# ps2.net
KiCad netlist of a schematic drawn in EAGLE
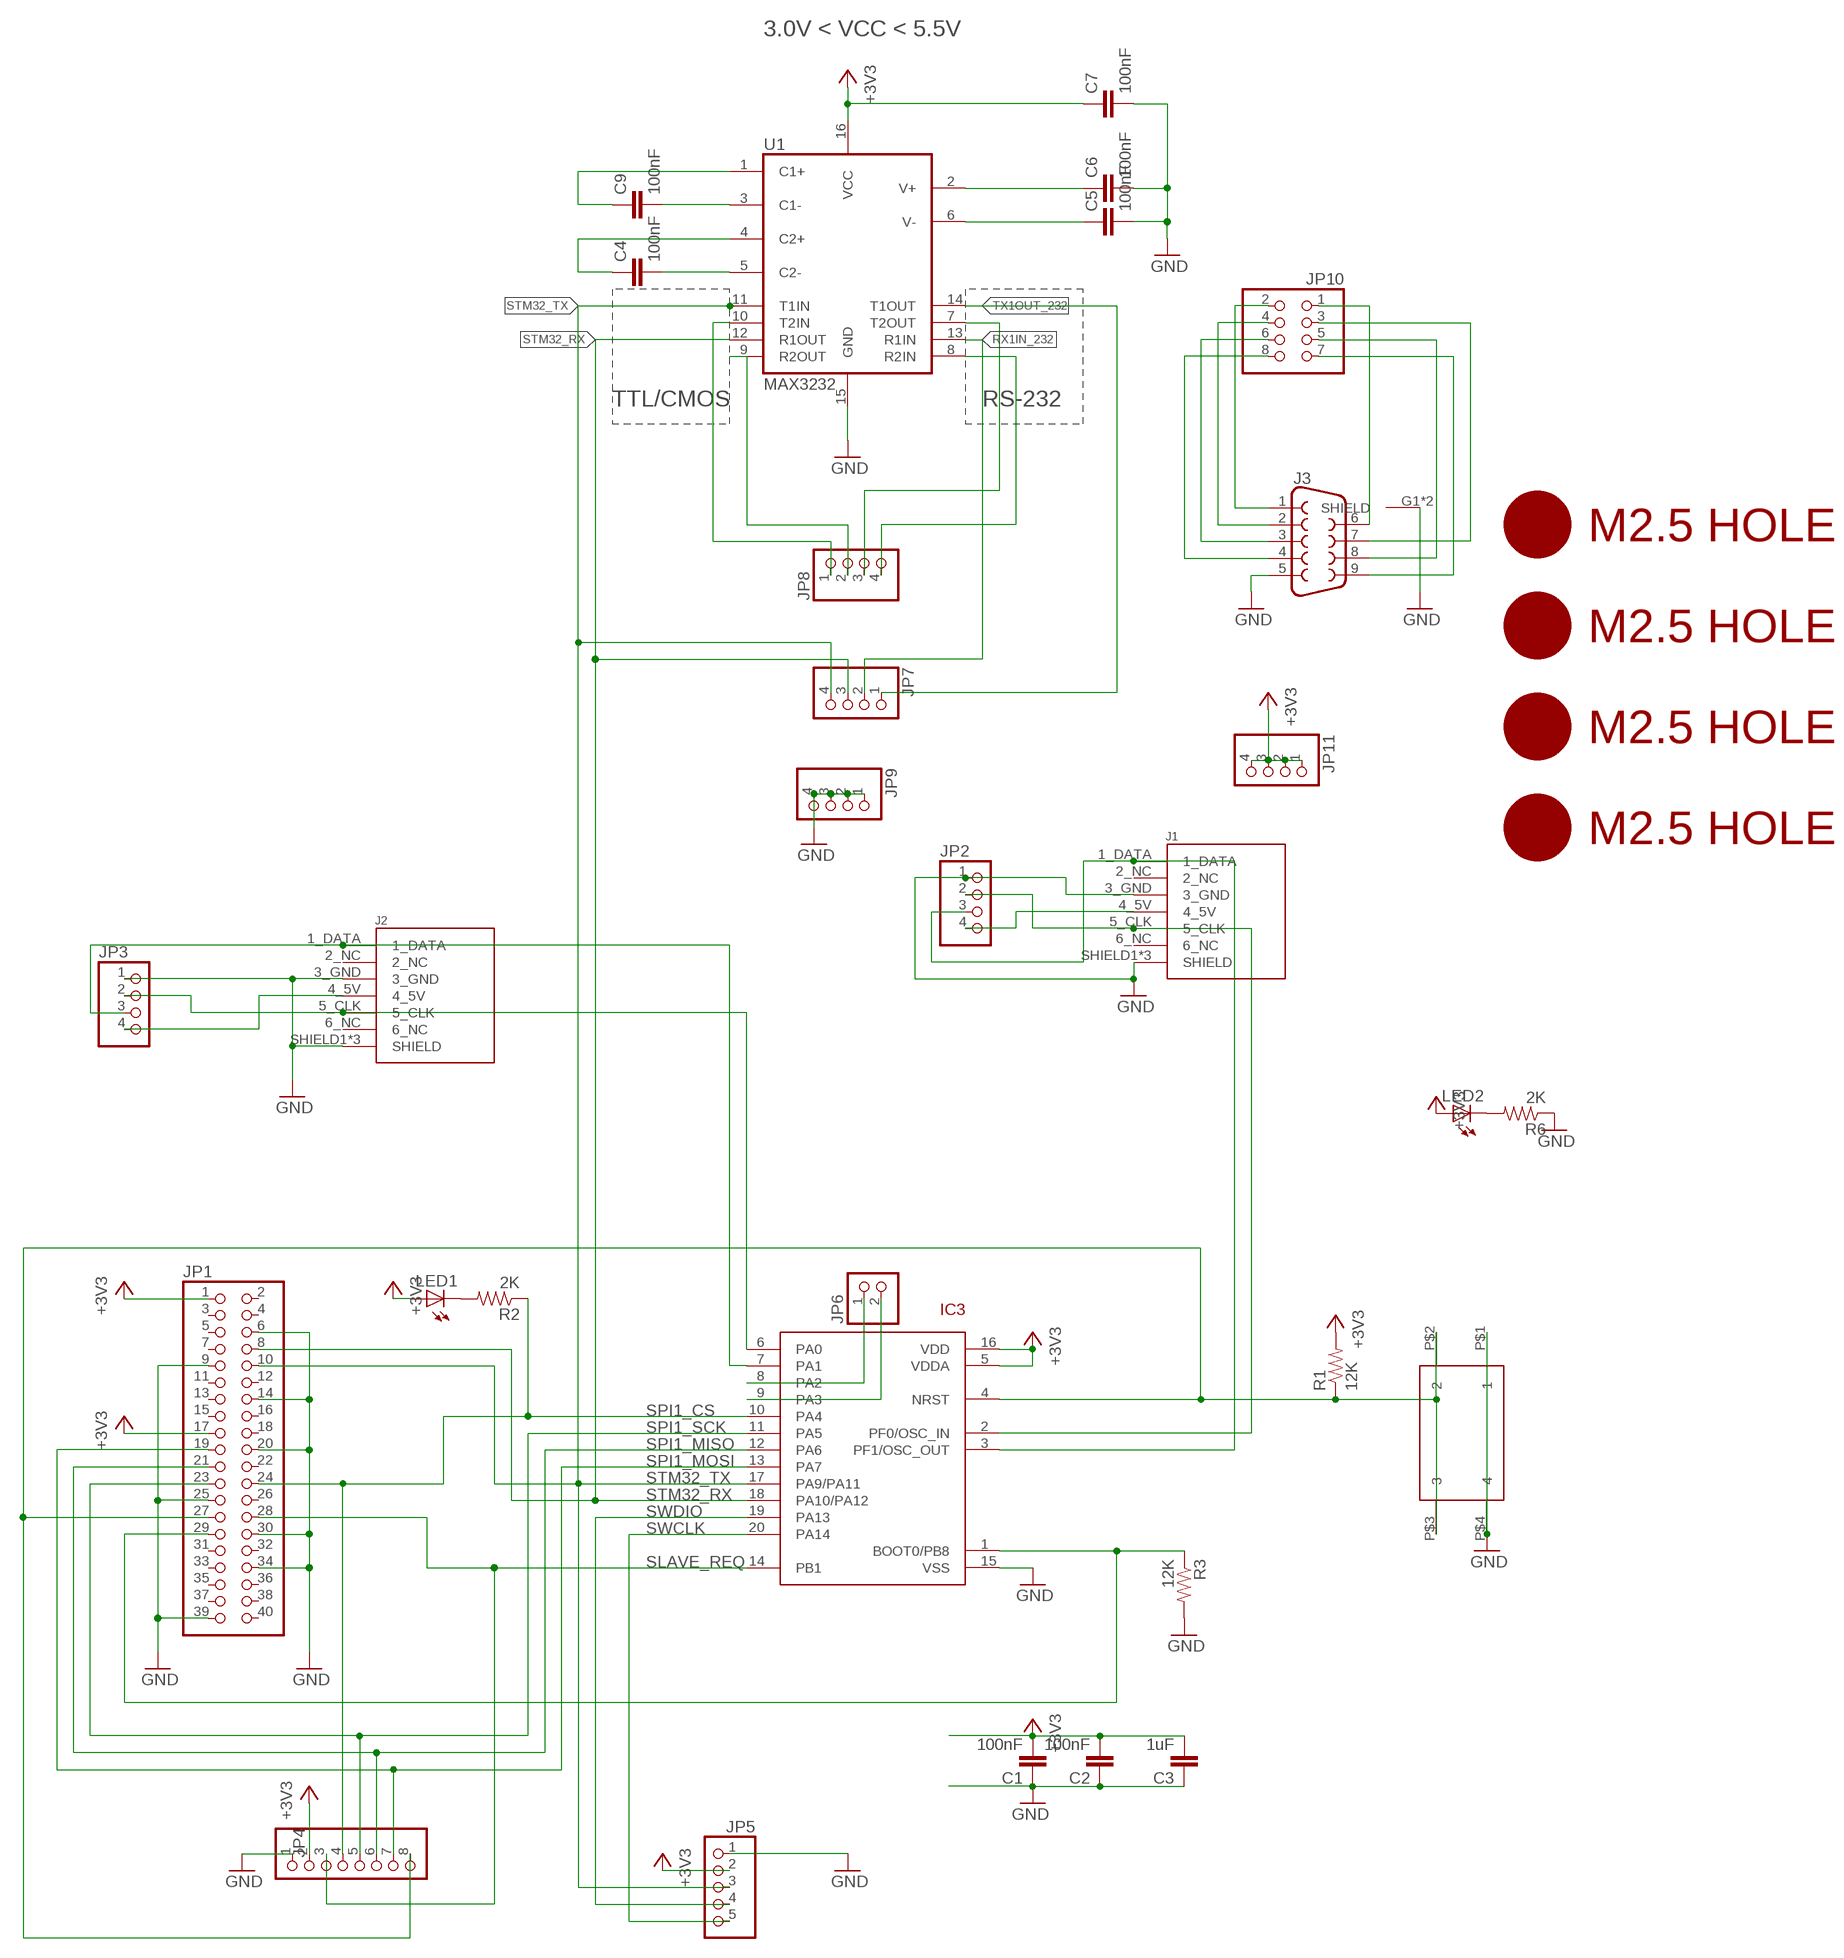
[diagram p0: schematic, sheet 1]

(export (version "E")
  (design (tool "Eeschema 10.0.6"))
  (components
    (comp (ref "C1")
      (value "100nF")
      (footprint "eagle-import:0805@1")
      (libsource (lib "eagle-import") (part "CAP0805"))
    )
    (comp (ref "C2")
      (value "100nF")
      (footprint "eagle-import:0805@1")
      (libsource (lib "eagle-import") (part "CAP0805"))
    )
    (comp (ref "C3")
      (value "1uF")
      (footprint "eagle-import:0805@1")
      (libsource (lib "eagle-import") (part "CAP0805"))
    )
    (comp (ref "C4")
      (value "100nF")
      (footprint "eagle-import:0805@1")
      (libsource (lib "eagle-import") (part "CAP0805"))
    )
    (comp (ref "C5")
      (value "100nF")
      (footprint "eagle-import:0805@1")
      (libsource (lib "eagle-import") (part "CAP0805"))
    )
    (comp (ref "C6")
      (value "100nF")
      (footprint "eagle-import:0805@1")
      (libsource (lib "eagle-import") (part "CAP0805"))
    )
    (comp (ref "C7")
      (value "100nF")
      (footprint "eagle-import:0805@1")
      (libsource (lib "eagle-import") (part "CAP0805"))
    )
    (comp (ref "C9")
      (value "100nF")
      (footprint "eagle-import:0805@1")
      (libsource (lib "eagle-import") (part "CAP0805"))
    )
    (comp (ref "IC3")
      (value "STM32F042F4")
      (footprint "eagle-import:TSSOP20")
      (libsource (lib "eagle-import") (part "STM32F042F4"))
    )
    (comp (ref "J1")
      (value "DIN7")
      (footprint "eagle-import:DIN7")
      (libsource (lib "eagle-import") (part "DIN7"))
    )
    (comp (ref "J2")
      (value "DIN7")
      (footprint "eagle-import:DIN7")
      (libsource (lib "eagle-import") (part "DIN7"))
    )
    (comp (ref "J3")
      (value "DB9MALE")
      (footprint "eagle-import:DB9_MALE")
      (libsource (lib "eagle-import") (part "DB9MALE"))
    )
    (comp (ref "JP1")
      (value "PINHD-2X20-BIG")
      (footprint "eagle-import:2X20-BIG")
      (libsource (lib "eagle-import") (part "PINHD-2X20-BIG"))
    )
    (comp (ref "JP2")
      (value "PINHD-1X4")
      (footprint "eagle-import:1X04")
      (libsource (lib "eagle-import") (part "PINHD-1X4"))
    )
    (comp (ref "JP3")
      (value "PINHD-1X4")
      (footprint "eagle-import:1X04")
      (libsource (lib "eagle-import") (part "PINHD-1X4"))
    )
    (comp (ref "JP4")
      (value "PINHD-1X8")
      (footprint "eagle-import:1X08")
      (libsource (lib "eagle-import") (part "PINHD-1X8"))
    )
    (comp (ref "JP5")
      (value "PINHD-1X5")
      (footprint "eagle-import:1X05")
      (libsource (lib "eagle-import") (part "PINHD-1X5"))
    )
    (comp (ref "JP6")
      (value "PINHD-1X2")
      (footprint "eagle-import:1X02")
      (libsource (lib "eagle-import") (part "PINHD-1X2"))
    )
    (comp (ref "JP7")
      (value "PINHD-1X4")
      (footprint "eagle-import:1X04")
      (libsource (lib "eagle-import") (part "PINHD-1X4"))
    )
    (comp (ref "JP8")
      (value "PINHD-1X4")
      (footprint "eagle-import:1X04")
      (libsource (lib "eagle-import") (part "PINHD-1X4"))
    )
    (comp (ref "JP9")
      (value "PINHD-1X4")
      (footprint "eagle-import:1X04")
      (libsource (lib "eagle-import") (part "PINHD-1X4"))
    )
    (comp (ref "JP10")
      (value "PINHD-2X4")
      (footprint "eagle-import:2X04")
      (libsource (lib "eagle-import") (part "PINHD-2X4"))
    )
    (comp (ref "JP11")
      (value "PINHD-1X4")
      (footprint "eagle-import:1X04")
      (libsource (lib "eagle-import") (part "PINHD-1X4"))
    )
    (comp (ref "LED1")
      (value "LEDCHIP-LED0805")
      (footprint "eagle-import:CHIP-LED0805")
      (libsource (lib "eagle-import") (part "LEDCHIP-LED0805"))
    )
    (comp (ref "LED2")
      (value "LEDCHIP-LED0805")
      (footprint "eagle-import:CHIP-LED0805")
      (libsource (lib "eagle-import") (part "LEDCHIP-LED0805"))
    )
    (comp (ref "R1")
      (value "12K")
      (footprint "eagle-import:0805")
      (libsource (lib "eagle-import") (part "RESISTOR0805-RES"))
    )
    (comp (ref "R2")
      (value "2K")
      (footprint "eagle-import:0805")
      (libsource (lib "eagle-import") (part "RESISTOR0805-RES"))
    )
    (comp (ref "R3")
      (value "12K")
      (footprint "eagle-import:0805")
      (libsource (lib "eagle-import") (part "RESISTOR0805-RES"))
    )
    (comp (ref "R6")
      (value "2K")
      (footprint "eagle-import:0805")
      (libsource (lib "eagle-import") (part "RESISTOR0805-RES"))
    )
    (comp (ref "SW4")
      (value "324_SW")
      (footprint "eagle-import:342_SWICH_FOOT")
      (libsource (lib "eagle-import") (part "324_SW"))
    )
    (comp (ref "U$2")
      (value "M2.5HOLE")
      (footprint "eagle-import:M2.5HOLE")
      (libsource (lib "eagle-import") (part "M2.5HOLE"))
    )
    (comp (ref "U$3")
      (value "M2.5HOLE")
      (footprint "eagle-import:M2.5HOLE")
      (libsource (lib "eagle-import") (part "M2.5HOLE"))
    )
    (comp (ref "U$4")
      (value "M2.5HOLE")
      (footprint "eagle-import:M2.5HOLE")
      (libsource (lib "eagle-import") (part "M2.5HOLE"))
    )
    (comp (ref "U$5")
      (value "M2.5HOLE")
      (footprint "eagle-import:M2.5HOLE")
      (libsource (lib "eagle-import") (part "M2.5HOLE"))
    )
    (comp (ref "U1")
      (value "MAX3232")
      (footprint "eagle-import:SO016")
      (libsource (lib "eagle-import") (part "MAX232SOIC16"))
    )
  )
  (nets
    (net (code "1") (name "+3V3") (class "Default")
      (node (ref "C1") (pin "2") (pinfunction "2_2") (pintype "passive"))
      (node (ref "C2") (pin "2") (pinfunction "2_2") (pintype "passive"))
      (node (ref "C3") (pin "2") (pinfunction "2_2") (pintype "passive"))
      (node (ref "C7") (pin "1") (pinfunction "1_1") (pintype "passive"))
      (node (ref "IC3") (pin "16") (pinfunction "VDD_16") (pintype "bidirectional"))
      (node (ref "IC3") (pin "5") (pinfunction "VDDA_5") (pintype "bidirectional"))
      (node (ref "JP1") (pin "1") (pinfunction "1_1") (pintype "passive"))
      (node (ref "JP1") (pin "17") (pinfunction "17_17") (pintype "passive"))
      (node (ref "JP11") (pin "1") (pinfunction "1_1") (pintype "passive"))
      (node (ref "JP11") (pin "2") (pinfunction "2_2") (pintype "passive"))
      (node (ref "JP11") (pin "3") (pinfunction "3_3") (pintype "passive"))
      (node (ref "JP11") (pin "4") (pinfunction "4_4") (pintype "passive"))
      (node (ref "JP4") (pin "2") (pinfunction "2_2") (pintype "passive"))
      (node (ref "JP5") (pin "2") (pinfunction "2_2") (pintype "passive"))
      (node (ref "LED1") (pin "A") (pinfunction "A_A") (pintype "passive"))
      (node (ref "LED2") (pin "A") (pinfunction "A_A") (pintype "passive"))
      (node (ref "R1") (pin "2") (pinfunction "2_2") (pintype "passive"))
      (node (ref "U1") (pin "16") (pinfunction "VCC_16") (pintype "bidirectional"))
    )
    (net (code "2") (name "/SLAVE_REQ") (class "Default")
      (node (ref "IC3") (pin "14") (pinfunction "PB1_14") (pintype "bidirectional"))
      (node (ref "JP1") (pin "28") (pinfunction "28_28") (pintype "passive"))
      (node (ref "JP4") (pin "3") (pinfunction "3_3") (pintype "passive"))
    )
    (net (code "3") (name "/SPI1_CS") (class "Default")
      (node (ref "IC3") (pin "10") (pinfunction "PA4_10") (pintype "bidirectional"))
      (node (ref "JP1") (pin "24") (pinfunction "24_24") (pintype "passive"))
      (node (ref "JP4") (pin "4") (pinfunction "4_4") (pintype "passive"))
      (node (ref "R2") (pin "1") (pinfunction "1_1") (pintype "passive"))
    )
    (net (code "4") (name "/SPI1_MISO") (class "Default")
      (node (ref "IC3") (pin "12") (pinfunction "PA6_12") (pintype "bidirectional"))
      (node (ref "JP1") (pin "21") (pinfunction "21_21") (pintype "passive"))
      (node (ref "JP4") (pin "6") (pinfunction "6_6") (pintype "passive"))
    )
    (net (code "5") (name "/SPI1_MOSI") (class "Default")
      (node (ref "IC3") (pin "13") (pinfunction "PA7_13") (pintype "bidirectional"))
      (node (ref "JP1") (pin "19") (pinfunction "19_19") (pintype "passive"))
      (node (ref "JP4") (pin "7") (pinfunction "7_7") (pintype "passive"))
    )
    (net (code "6") (name "/SPI1_SCK") (class "Default")
      (node (ref "IC3") (pin "11") (pinfunction "PA5_11") (pintype "bidirectional"))
      (node (ref "JP1") (pin "23") (pinfunction "23_23") (pintype "passive"))
      (node (ref "JP4") (pin "5") (pinfunction "5_5") (pintype "passive"))
    )
    (net (code "7") (name "/SWCLK") (class "Default")
      (node (ref "IC3") (pin "20") (pinfunction "PA14_20") (pintype "bidirectional"))
      (node (ref "JP5") (pin "5") (pinfunction "5_5") (pintype "passive"))
    )
    (net (code "8") (name "/SWDIO") (class "Default")
      (node (ref "IC3") (pin "19") (pinfunction "PA13_19") (pintype "bidirectional"))
      (node (ref "JP5") (pin "4") (pinfunction "4_4") (pintype "passive"))
    )
    (net (code "9") (name "GND") (class "Default")
      (node (ref "C1") (pin "1") (pinfunction "1_1") (pintype "passive"))
      (node (ref "C2") (pin "1") (pinfunction "1_1") (pintype "passive"))
      (node (ref "C3") (pin "1") (pinfunction "1_1") (pintype "passive"))
      (node (ref "C5") (pin "2") (pinfunction "2_2") (pintype "passive"))
      (node (ref "C6") (pin "2") (pinfunction "2_2") (pintype "passive"))
      (node (ref "C7") (pin "2") (pinfunction "2_2") (pintype "passive"))
      (node (ref "IC3") (pin "15") (pinfunction "VSS_15") (pintype "bidirectional"))
      (node (ref "J1") (pin "3_GND") (pinfunction "3_GND_3_GND") (pintype "bidirectional"))
      (node (ref "J1") (pin "SHIELD1") (pinfunction "SHIELD_SHIELD1") (pintype "bidirectional"))
      (node (ref "J1") (pin "SHIELD2") (pinfunction "SHIELD_SHIELD2") (pintype "bidirectional"))
      (node (ref "J1") (pin "SHIELD3") (pinfunction "SHIELD_SHIELD3") (pintype "bidirectional"))
      (node (ref "J2") (pin "3_GND") (pinfunction "3_GND_3_GND") (pintype "bidirectional"))
      (node (ref "J2") (pin "SHIELD1") (pinfunction "SHIELD_SHIELD1") (pintype "bidirectional"))
      (node (ref "J2") (pin "SHIELD2") (pinfunction "SHIELD_SHIELD2") (pintype "bidirectional"))
      (node (ref "J2") (pin "SHIELD3") (pinfunction "SHIELD_SHIELD3") (pintype "bidirectional"))
      (node (ref "J3") (pin "5") (pinfunction "5_5") (pintype "passive"))
      (node (ref "J3") (pin "G1") (pinfunction "SHIELD_G1") (pintype "bidirectional"))
      (node (ref "J3") (pin "G2") (pinfunction "SHIELD_G2") (pintype "bidirectional"))
      (node (ref "JP1") (pin "14") (pinfunction "14_14") (pintype "passive"))
      (node (ref "JP1") (pin "20") (pinfunction "20_20") (pintype "passive"))
      (node (ref "JP1") (pin "25") (pinfunction "25_25") (pintype "passive"))
      (node (ref "JP1") (pin "30") (pinfunction "30_30") (pintype "passive"))
      (node (ref "JP1") (pin "34") (pinfunction "34_34") (pintype "passive"))
      (node (ref "JP1") (pin "39") (pinfunction "39_39") (pintype "passive"))
      (node (ref "JP1") (pin "6") (pinfunction "6_6") (pintype "passive"))
      (node (ref "JP1") (pin "9") (pinfunction "9_9") (pintype "passive"))
      (node (ref "JP2") (pin "1") (pinfunction "1_1") (pintype "passive"))
      (node (ref "JP3") (pin "1") (pinfunction "1_1") (pintype "passive"))
      (node (ref "JP4") (pin "1") (pinfunction "1_1") (pintype "passive"))
      (node (ref "JP5") (pin "1") (pinfunction "1_1") (pintype "passive"))
      (node (ref "JP9") (pin "1") (pinfunction "1_1") (pintype "passive"))
      (node (ref "JP9") (pin "2") (pinfunction "2_2") (pintype "passive"))
      (node (ref "JP9") (pin "3") (pinfunction "3_3") (pintype "passive"))
      (node (ref "JP9") (pin "4") (pinfunction "4_4") (pintype "passive"))
      (node (ref "R3") (pin "2") (pinfunction "2_2") (pintype "passive"))
      (node (ref "R6") (pin "1") (pinfunction "1_1") (pintype "passive"))
      (node (ref "SW4") (pin "P$1") (pinfunction "1_P$1") (pintype "bidirectional"))
      (node (ref "SW4") (pin "P$4") (pinfunction "4_P$4") (pintype "bidirectional"))
      (node (ref "U1") (pin "15") (pinfunction "GND_15") (pintype "bidirectional"))
    )
    (net (code "10") (name "Net-(IC3-BOOT0{slash}PB8)") (class "Default")
      (node (ref "IC3") (pin "1") (pinfunction "BOOT0/PB8_1") (pintype "bidirectional"))
      (node (ref "JP1") (pin "29") (pinfunction "29_29") (pintype "passive"))
      (node (ref "R3") (pin "1") (pinfunction "1_1") (pintype "passive"))
    )
    (net (code "11") (name "Net-(IC3-NRST)") (class "Default")
      (node (ref "IC3") (pin "4") (pinfunction "NRST_4") (pintype "bidirectional"))
      (node (ref "JP1") (pin "27") (pinfunction "27_27") (pintype "passive"))
      (node (ref "JP4") (pin "8") (pinfunction "8_8") (pintype "passive"))
      (node (ref "R1") (pin "1") (pinfunction "1_1") (pintype "passive"))
      (node (ref "SW4") (pin "P$2") (pinfunction "2_P$2") (pintype "bidirectional"))
      (node (ref "SW4") (pin "P$3") (pinfunction "3_P$3") (pintype "bidirectional"))
    )
    (net (code "12") (name "Net-(IC3-PA0)") (class "Default")
      (node (ref "IC3") (pin "6") (pinfunction "PA0_6") (pintype "bidirectional"))
      (node (ref "J2") (pin "5_CLK") (pinfunction "5_CLK_5_CLK") (pintype "bidirectional"))
      (node (ref "JP3") (pin "2") (pinfunction "2_2") (pintype "passive"))
    )
    (net (code "13") (name "Net-(IC3-PA1)") (class "Default")
      (node (ref "IC3") (pin "7") (pinfunction "PA1_7") (pintype "bidirectional"))
      (node (ref "J2") (pin "1_DATA") (pinfunction "1_DATA_1_DATA") (pintype "bidirectional"))
      (node (ref "JP3") (pin "3") (pinfunction "3_3") (pintype "passive"))
    )
    (net (code "14") (name "Net-(IC3-PA2)") (class "Default")
      (node (ref "IC3") (pin "8") (pinfunction "PA2_8") (pintype "bidirectional"))
      (node (ref "JP6") (pin "1") (pinfunction "1_1") (pintype "passive"))
    )
    (net (code "15") (name "Net-(IC3-PA3)") (class "Default")
      (node (ref "IC3") (pin "9") (pinfunction "PA3_9") (pintype "bidirectional"))
      (node (ref "JP6") (pin "2") (pinfunction "2_2") (pintype "passive"))
    )
    (net (code "16") (name "Net-(IC3-PF0{slash}OSC_IN)") (class "Default")
      (node (ref "IC3") (pin "2") (pinfunction "PF0/OSC_IN_2") (pintype "bidirectional"))
      (node (ref "J1") (pin "5_CLK") (pinfunction "5_CLK_5_CLK") (pintype "bidirectional"))
      (node (ref "JP2") (pin "2") (pinfunction "2_2") (pintype "passive"))
    )
    (net (code "17") (name "Net-(IC3-PF1{slash}OSC_OUT)") (class "Default")
      (node (ref "IC3") (pin "3") (pinfunction "PF1/OSC_OUT_3") (pintype "bidirectional"))
      (node (ref "J1") (pin "1_DATA") (pinfunction "1_DATA_1_DATA") (pintype "bidirectional"))
      (node (ref "JP2") (pin "3") (pinfunction "3_3") (pintype "passive"))
    )
    (net (code "18") (name "Net-(J1-Pad4_5V)") (class "Default")
      (node (ref "J1") (pin "4_5V") (pinfunction "4_5V_4_5V") (pintype "bidirectional"))
      (node (ref "JP2") (pin "4") (pinfunction "4_4") (pintype "passive"))
    )
    (net (code "19") (name "Net-(J2-Pad4_5V)") (class "Default")
      (node (ref "J2") (pin "4_5V") (pinfunction "4_5V_4_5V") (pintype "bidirectional"))
      (node (ref "JP3") (pin "4") (pinfunction "4_4") (pintype "passive"))
    )
    (net (code "20") (name "Net-(J3-Pad1)") (class "Default")
      (node (ref "J3") (pin "1") (pinfunction "1_1") (pintype "passive"))
      (node (ref "JP10") (pin "2") (pinfunction "2_2") (pintype "passive"))
    )
    (net (code "21") (name "Net-(J3-Pad2)") (class "Default")
      (node (ref "J3") (pin "2") (pinfunction "2_2") (pintype "passive"))
      (node (ref "JP10") (pin "4") (pinfunction "4_4") (pintype "passive"))
    )
    (net (code "22") (name "Net-(J3-Pad3)") (class "Default")
      (node (ref "J3") (pin "3") (pinfunction "3_3") (pintype "passive"))
      (node (ref "JP10") (pin "6") (pinfunction "6_6") (pintype "passive"))
    )
    (net (code "23") (name "Net-(J3-Pad4)") (class "Default")
      (node (ref "J3") (pin "4") (pinfunction "4_4") (pintype "passive"))
      (node (ref "JP10") (pin "8") (pinfunction "8_8") (pintype "passive"))
    )
    (net (code "24") (name "Net-(J3-Pad6)") (class "Default")
      (node (ref "J3") (pin "6") (pinfunction "6_6") (pintype "passive"))
      (node (ref "JP10") (pin "1") (pinfunction "1_1") (pintype "passive"))
    )
    (net (code "25") (name "Net-(J3-Pad7)") (class "Default")
      (node (ref "J3") (pin "7") (pinfunction "7_7") (pintype "passive"))
      (node (ref "JP10") (pin "3") (pinfunction "3_3") (pintype "passive"))
    )
    (net (code "26") (name "Net-(J3-Pad8)") (class "Default")
      (node (ref "J3") (pin "8") (pinfunction "8_8") (pintype "passive"))
      (node (ref "JP10") (pin "5") (pinfunction "5_5") (pintype "passive"))
    )
    (net (code "27") (name "Net-(J3-Pad9)") (class "Default")
      (node (ref "J3") (pin "9") (pinfunction "9_9") (pintype "passive"))
      (node (ref "JP10") (pin "7") (pinfunction "7_7") (pintype "passive"))
    )
    (net (code "28") (name "Net-(LED1-PadC)") (class "Default")
      (node (ref "LED1") (pin "C") (pinfunction "C_C") (pintype "passive"))
      (node (ref "R2") (pin "2") (pinfunction "2_2") (pintype "passive"))
    )
    (net (code "29") (name "Net-(LED2-PadC)") (class "Default")
      (node (ref "LED2") (pin "C") (pinfunction "C_C") (pintype "passive"))
      (node (ref "R6") (pin "2") (pinfunction "2_2") (pintype "passive"))
    )
    (net (code "30") (name "Net-(U1-C1+)") (class "Default")
      (node (ref "C9") (pin "1") (pinfunction "1_1") (pintype "passive"))
      (node (ref "U1") (pin "1") (pinfunction "C1+_1") (pintype "bidirectional"))
    )
    (net (code "31") (name "Net-(U1-C1-)") (class "Default")
      (node (ref "C9") (pin "2") (pinfunction "2_2") (pintype "passive"))
      (node (ref "U1") (pin "3") (pinfunction "C1-_3") (pintype "bidirectional"))
    )
    (net (code "32") (name "Net-(U1-C2+)") (class "Default")
      (node (ref "C4") (pin "1") (pinfunction "1_1") (pintype "passive"))
      (node (ref "U1") (pin "4") (pinfunction "C2+_4") (pintype "bidirectional"))
    )
    (net (code "33") (name "Net-(U1-C2-)") (class "Default")
      (node (ref "C4") (pin "2") (pinfunction "2_2") (pintype "passive"))
      (node (ref "U1") (pin "5") (pinfunction "C2-_5") (pintype "bidirectional"))
    )
    (net (code "34") (name "Net-(U1-R2IN)") (class "Default")
      (node (ref "JP8") (pin "4") (pinfunction "4_4") (pintype "passive"))
      (node (ref "U1") (pin "8") (pinfunction "R2IN_8") (pintype "input"))
    )
    (net (code "35") (name "Net-(U1-R2OUT)") (class "Default")
      (node (ref "JP8") (pin "2") (pinfunction "2_2") (pintype "passive"))
      (node (ref "U1") (pin "9") (pinfunction "R2OUT_9") (pintype "output"))
    )
    (net (code "36") (name "Net-(U1-T2IN)") (class "Default")
      (node (ref "JP8") (pin "1") (pinfunction "1_1") (pintype "passive"))
      (node (ref "U1") (pin "10") (pinfunction "T2IN_10") (pintype "input"))
    )
    (net (code "37") (name "Net-(U1-T2OUT)") (class "Default")
      (node (ref "JP8") (pin "3") (pinfunction "3_3") (pintype "passive"))
      (node (ref "U1") (pin "7") (pinfunction "T2OUT_7") (pintype "output"))
    )
    (net (code "38") (name "Net-(U1-V+)") (class "Default")
      (node (ref "C6") (pin "1") (pinfunction "1_1") (pintype "passive"))
      (node (ref "U1") (pin "2") (pinfunction "V+_2") (pintype "bidirectional"))
    )
    (net (code "39") (name "Net-(U1-V-)") (class "Default")
      (node (ref "C5") (pin "1") (pinfunction "1_1") (pintype "passive"))
      (node (ref "U1") (pin "6") (pinfunction "V-_6") (pintype "bidirectional"))
    )
    (net (code "40") (name "RX1IN_232") (class "Default")
      (node (ref "JP7") (pin "2") (pinfunction "2_2") (pintype "passive"))
      (node (ref "U1") (pin "13") (pinfunction "R1IN_13") (pintype "input"))
    )
    (net (code "41") (name "STM32_RX") (class "Default")
      (node (ref "IC3") (pin "18") (pinfunction "PA10/PA12_18") (pintype "bidirectional"))
      (node (ref "JP1") (pin "8") (pinfunction "8_8") (pintype "passive"))
      (node (ref "JP7") (pin "3") (pinfunction "3_3") (pintype "passive"))
      (node (ref "U1") (pin "12") (pinfunction "R1OUT_12") (pintype "output"))
    )
    (net (code "42") (name "STM32_TX") (class "Default")
      (node (ref "IC3") (pin "17") (pinfunction "PA9/PA11_17") (pintype "bidirectional"))
      (node (ref "JP1") (pin "10") (pinfunction "10_10") (pintype "passive"))
      (node (ref "JP5") (pin "3") (pinfunction "3_3") (pintype "passive"))
      (node (ref "JP7") (pin "4") (pinfunction "4_4") (pintype "passive"))
      (node (ref "U1") (pin "11") (pinfunction "T1IN_11") (pintype "input"))
    )
    (net (code "43") (name "TX1OUT_232") (class "Default")
      (node (ref "JP7") (pin "1") (pinfunction "1_1") (pintype "passive"))
      (node (ref "U1") (pin "14") (pinfunction "T1OUT_14") (pintype "output"))
    )
    (net (code "44") (name "unconnected-(J1-Pad2_NC)") (class "Default")
      (node (ref "J1") (pin "2_NC") (pinfunction "2_NC_2_NC") (pintype "bidirectional"))
    )
    (net (code "45") (name "unconnected-(J1-Pad6_NC)") (class "Default")
      (node (ref "J1") (pin "6_NC") (pinfunction "6_NC_6_NC") (pintype "bidirectional"))
    )
    (net (code "46") (name "unconnected-(J2-Pad2_NC)") (class "Default")
      (node (ref "J2") (pin "2_NC") (pinfunction "2_NC_2_NC") (pintype "bidirectional"))
    )
    (net (code "47") (name "unconnected-(J2-Pad6_NC)") (class "Default")
      (node (ref "J2") (pin "6_NC") (pinfunction "6_NC_6_NC") (pintype "bidirectional"))
    )
    (net (code "48") (name "unconnected-(JP1-Pad2)") (class "Default")
      (node (ref "JP1") (pin "2") (pinfunction "2_2") (pintype "passive"))
    )
    (net (code "49") (name "unconnected-(JP1-Pad3)") (class "Default")
      (node (ref "JP1") (pin "3") (pinfunction "3_3") (pintype "passive"))
    )
    (net (code "50") (name "unconnected-(JP1-Pad4)") (class "Default")
      (node (ref "JP1") (pin "4") (pinfunction "4_4") (pintype "passive"))
    )
    (net (code "51") (name "unconnected-(JP1-Pad5)") (class "Default")
      (node (ref "JP1") (pin "5") (pinfunction "5_5") (pintype "passive"))
    )
    (net (code "52") (name "unconnected-(JP1-Pad7)") (class "Default")
      (node (ref "JP1") (pin "7") (pinfunction "7_7") (pintype "passive"))
    )
    (net (code "53") (name "unconnected-(JP1-Pad11)") (class "Default")
      (node (ref "JP1") (pin "11") (pinfunction "11_11") (pintype "passive"))
    )
    (net (code "54") (name "unconnected-(JP1-Pad12)") (class "Default")
      (node (ref "JP1") (pin "12") (pinfunction "12_12") (pintype "passive"))
    )
    (net (code "55") (name "unconnected-(JP1-Pad13)") (class "Default")
      (node (ref "JP1") (pin "13") (pinfunction "13_13") (pintype "passive"))
    )
    (net (code "56") (name "unconnected-(JP1-Pad15)") (class "Default")
      (node (ref "JP1") (pin "15") (pinfunction "15_15") (pintype "passive"))
    )
    (net (code "57") (name "unconnected-(JP1-Pad16)") (class "Default")
      (node (ref "JP1") (pin "16") (pinfunction "16_16") (pintype "passive"))
    )
    (net (code "58") (name "unconnected-(JP1-Pad18)") (class "Default")
      (node (ref "JP1") (pin "18") (pinfunction "18_18") (pintype "passive"))
    )
    (net (code "59") (name "unconnected-(JP1-Pad22)") (class "Default")
      (node (ref "JP1") (pin "22") (pinfunction "22_22") (pintype "passive"))
    )
    (net (code "60") (name "unconnected-(JP1-Pad26)") (class "Default")
      (node (ref "JP1") (pin "26") (pinfunction "26_26") (pintype "passive"))
    )
    (net (code "61") (name "unconnected-(JP1-Pad31)") (class "Default")
      (node (ref "JP1") (pin "31") (pinfunction "31_31") (pintype "passive"))
    )
    (net (code "62") (name "unconnected-(JP1-Pad32)") (class "Default")
      (node (ref "JP1") (pin "32") (pinfunction "32_32") (pintype "passive"))
    )
    (net (code "63") (name "unconnected-(JP1-Pad33)") (class "Default")
      (node (ref "JP1") (pin "33") (pinfunction "33_33") (pintype "passive"))
    )
    (net (code "64") (name "unconnected-(JP1-Pad35)") (class "Default")
      (node (ref "JP1") (pin "35") (pinfunction "35_35") (pintype "passive"))
    )
    (net (code "65") (name "unconnected-(JP1-Pad36)") (class "Default")
      (node (ref "JP1") (pin "36") (pinfunction "36_36") (pintype "passive"))
    )
    (net (code "66") (name "unconnected-(JP1-Pad37)") (class "Default")
      (node (ref "JP1") (pin "37") (pinfunction "37_37") (pintype "passive"))
    )
    (net (code "67") (name "unconnected-(JP1-Pad38)") (class "Default")
      (node (ref "JP1") (pin "38") (pinfunction "38_38") (pintype "passive"))
    )
    (net (code "68") (name "unconnected-(JP1-Pad40)") (class "Default")
      (node (ref "JP1") (pin "40") (pinfunction "40_40") (pintype "passive"))
    )
  )
)
